# DeepSpace.net
KiCad netlist of a schematic drawn in EAGLE
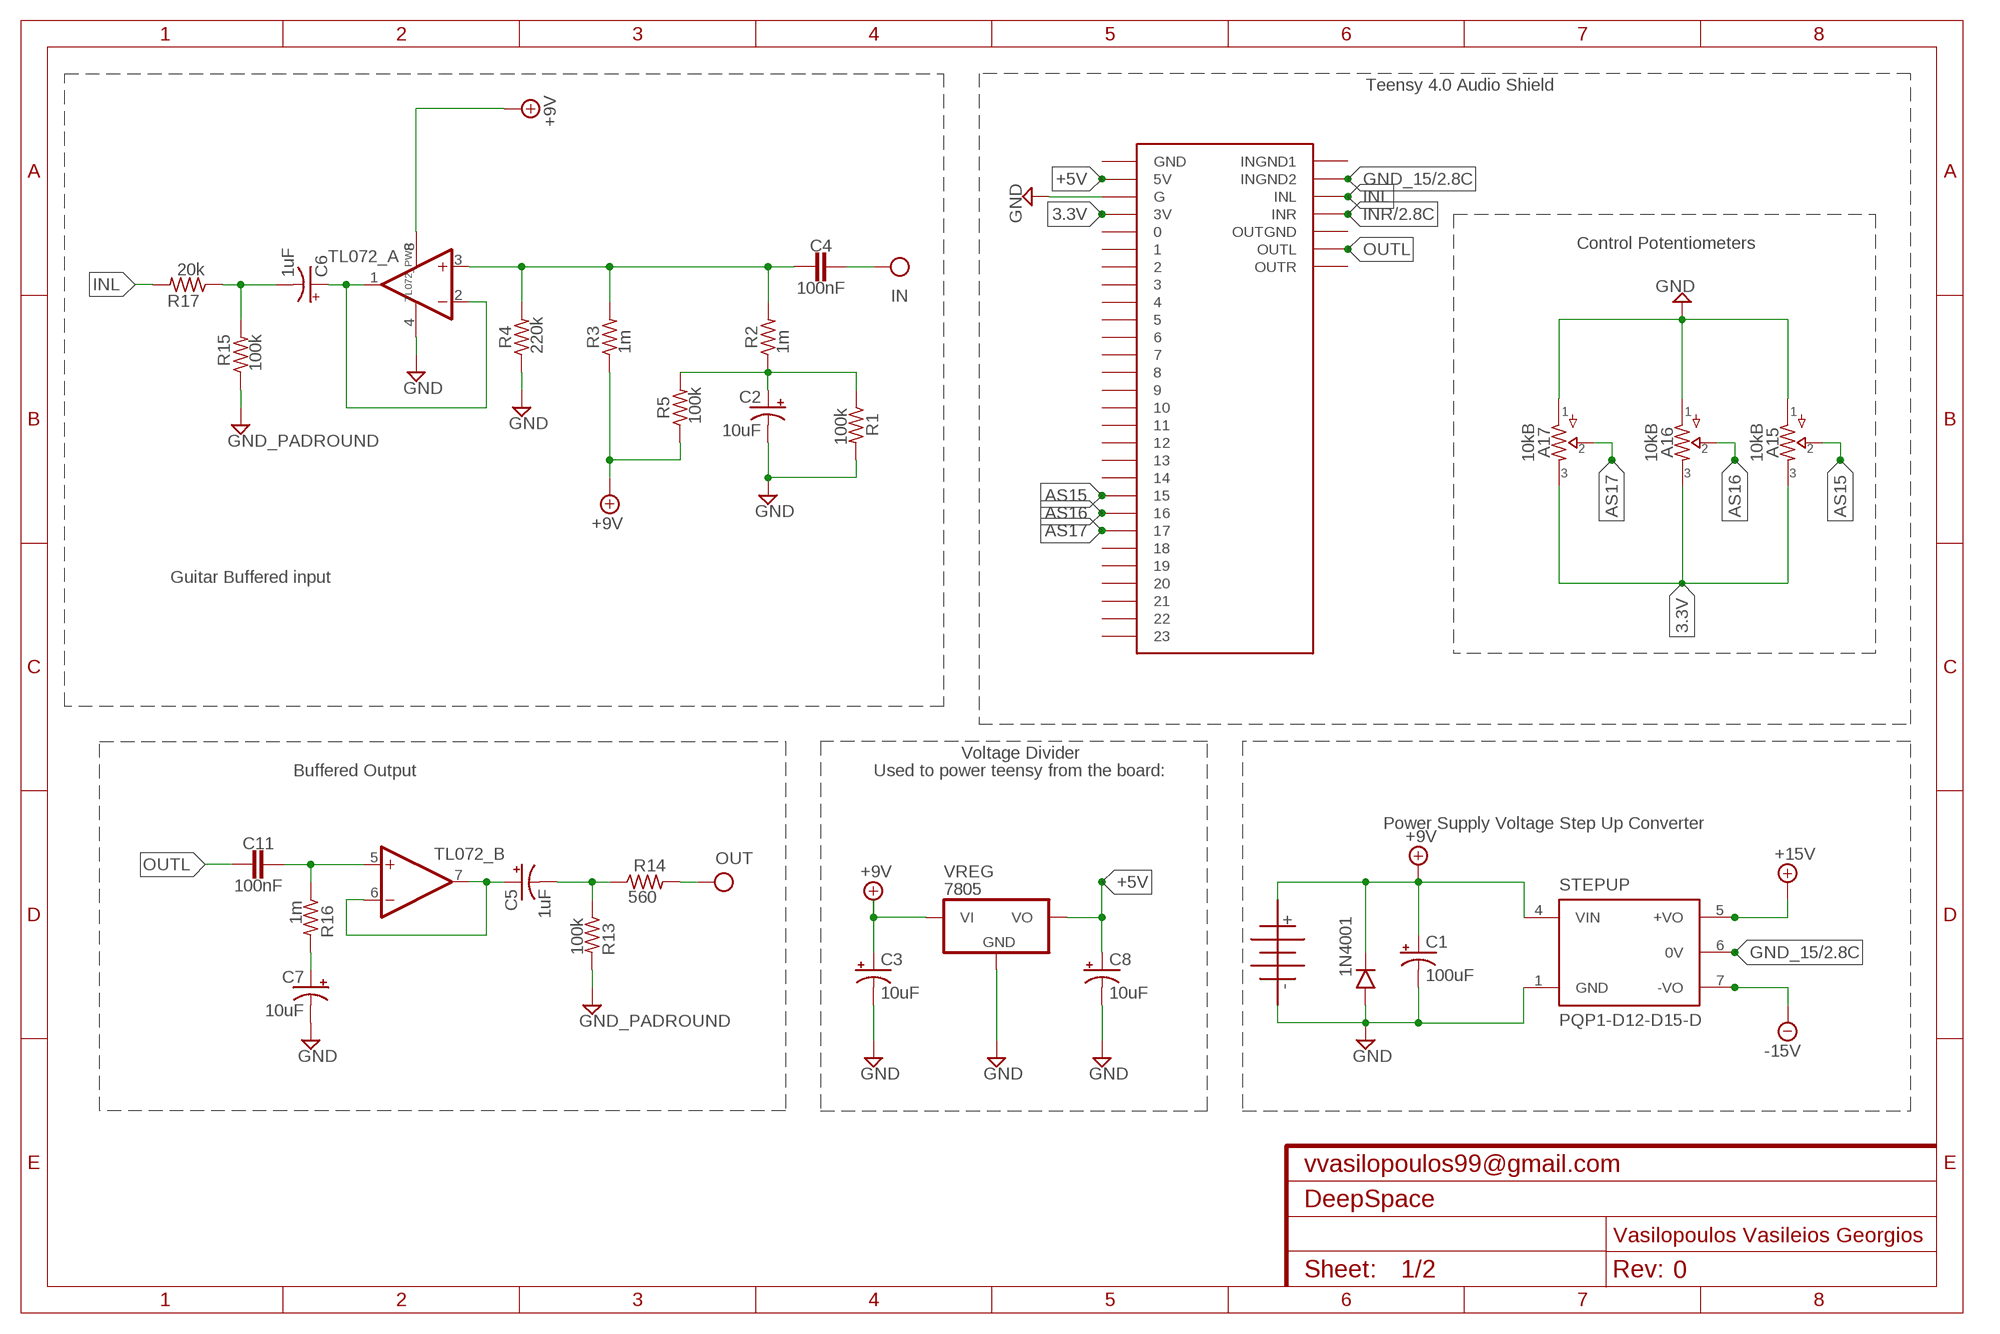
[diagram p0: schematic, sheet 1]
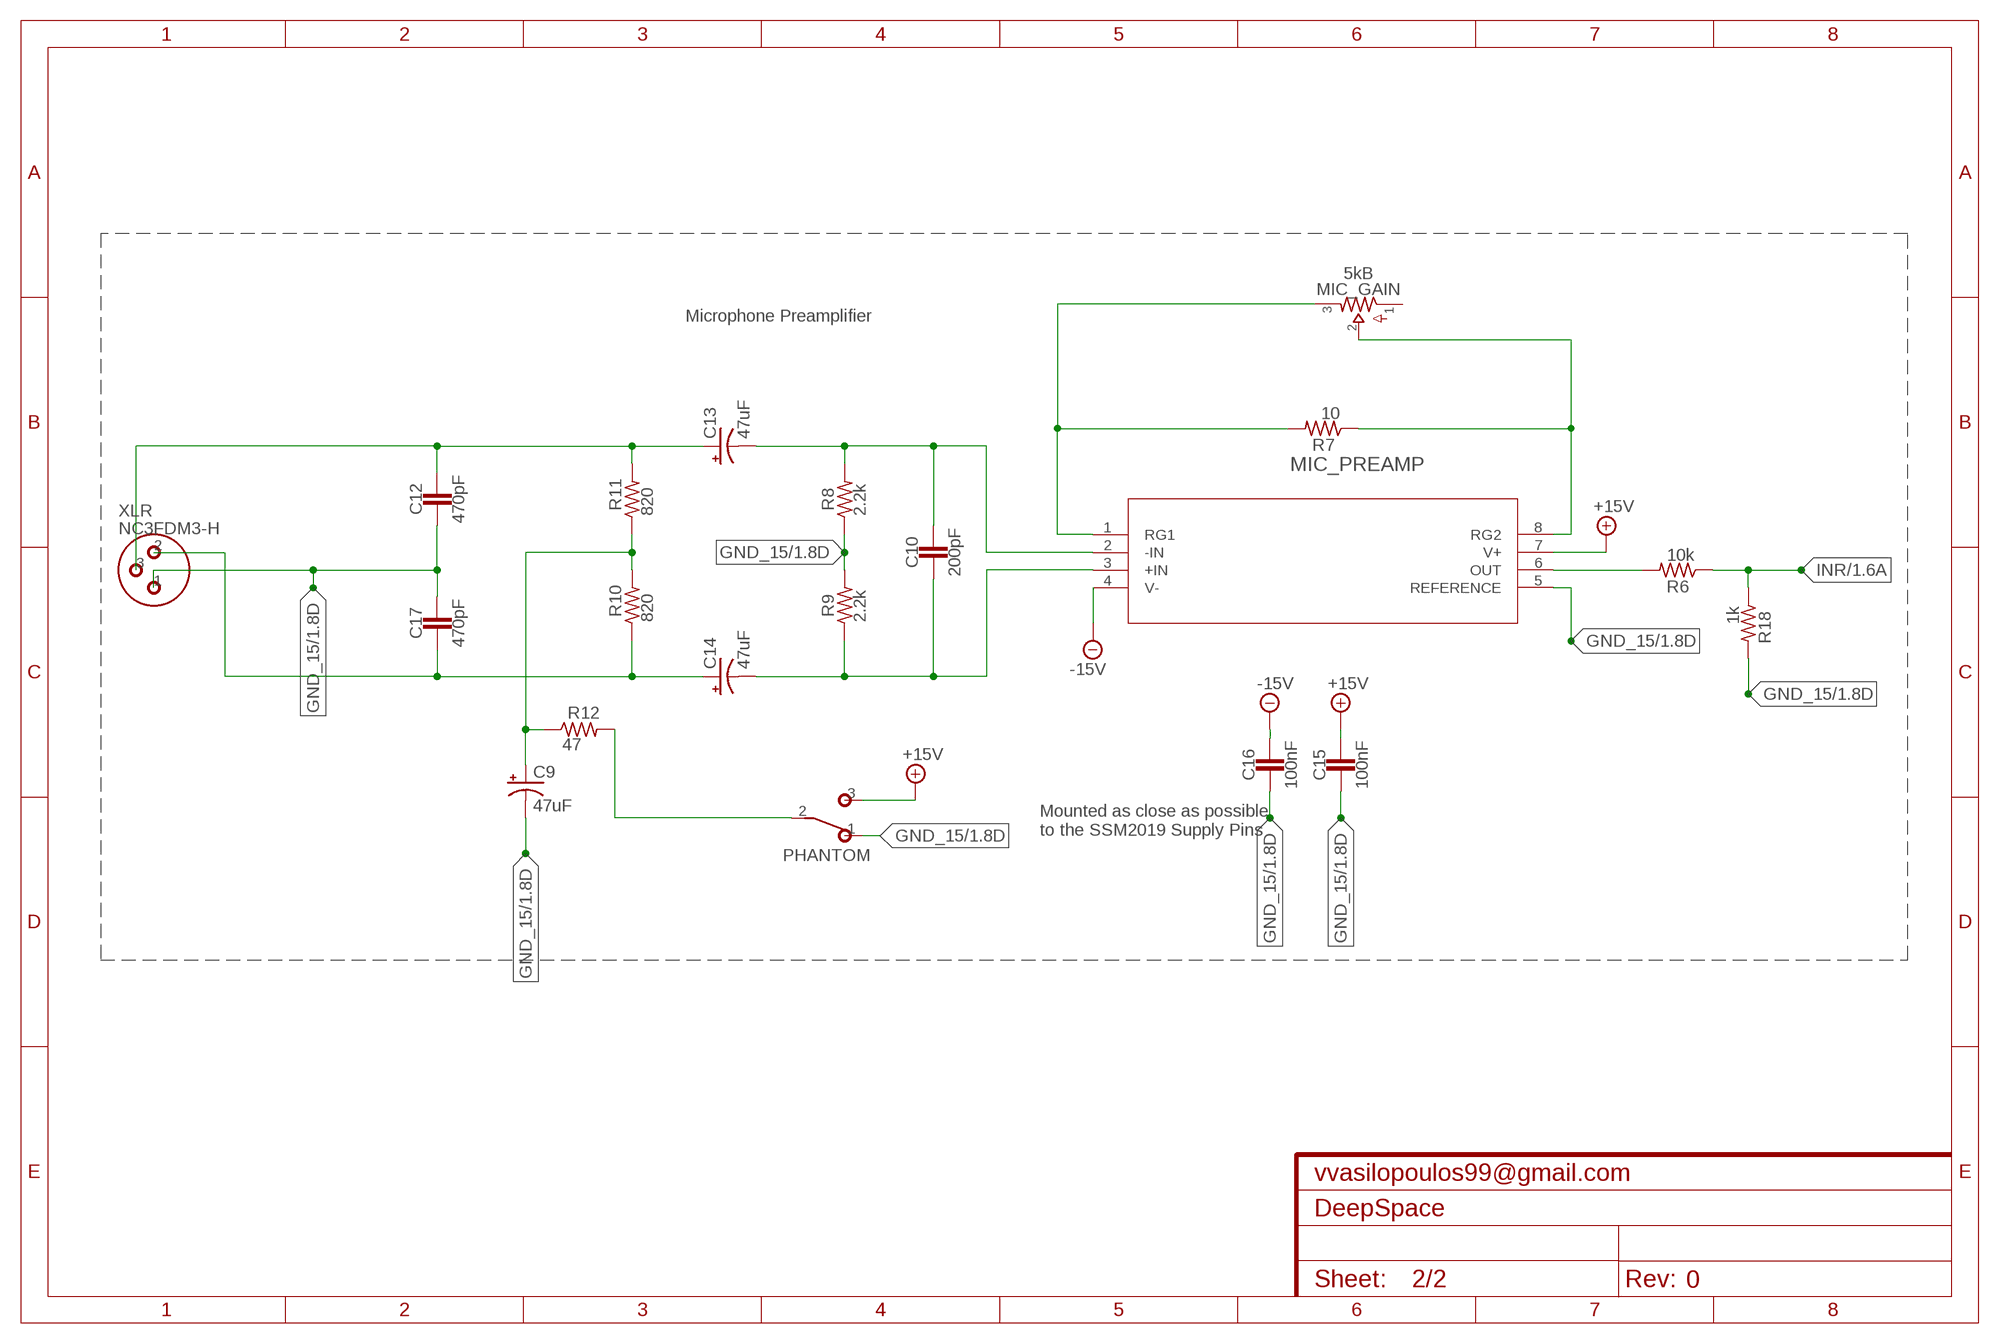
[diagram p1: schematic, sheet 2]

(export (version "E")
  (design (tool "Eeschema 10.0.6"))
  (components
    (comp (ref "C9")
      (value "47uF")
      (footprint "eagle-import:050_020_1")
      (libsource (lib "eagle-import") (part "0501"))
    )
    (comp (ref "C10")
      (value "200pF")
      (footprint "eagle-import:0.2_.SML")
      (libsource (lib "eagle-import") (part "CAP.2"))
    )
    (comp (ref "C12")
      (value "470pF")
      (footprint "eagle-import:0.2_.SML")
      (libsource (lib "eagle-import") (part "CAP.2"))
    )
    (comp (ref "C13")
      (value "47uF")
      (footprint "eagle-import:063_025")
      (libsource (lib "eagle-import") (part "0631"))
    )
    (comp (ref "C14")
      (value "47uF")
      (footprint "eagle-import:063_025")
      (libsource (lib "eagle-import") (part "0631"))
    )
    (comp (ref "C15")
      (value "100nF")
      (footprint "eagle-import:0.2_.SML")
      (libsource (lib "eagle-import") (part "CAP.2"))
    )
    (comp (ref "C16")
      (value "100nF")
      (footprint "eagle-import:0.2_.SML")
      (libsource (lib "eagle-import") (part "CAP.2"))
    )
    (comp (ref "C17")
      (value "470pF")
      (footprint "eagle-import:0.2_.SML")
      (libsource (lib "eagle-import") (part "CAP.2"))
    )
    (comp (ref "MIC_GAIN")
      (value "5kB")
      (footprint "eagle-import:TRIM1")
      (libsource (lib "eagle-import") (part "TRIMMER"))
    )
    (comp (ref "MIC_PREAMP")
      (value "SSM2019BNZ")
      (footprint "eagle-import:N_8_ADI")
      (fields (field (name "MF") "ANALOG DEVICES") (field (name "MPN") "SSM2019BRNZ"))
      (libsource (lib "eagle-import") (part "SSM2019BNZ"))
    )
    (comp (ref "PHANTOM")
      (value "SPDTPADS")
      (footprint "eagle-import:SPDT")
      (libsource (lib "eagle-import") (part "SPDTPADS"))
    )
    (comp (ref "R6")
      (value "10k")
      (footprint "eagle-import:R0207_3")
      (libsource (lib "eagle-import") (part "RESISTORS.3B"))
    )
    (comp (ref "R7")
      (value "10")
      (footprint "eagle-import:R0207_3")
      (libsource (lib "eagle-import") (part "RESISTORS.3B"))
    )
    (comp (ref "R8")
      (value "2.2k")
      (footprint "eagle-import:R0207_3")
      (libsource (lib "eagle-import") (part "RESISTORS.3B"))
    )
    (comp (ref "R9")
      (value "2.2k")
      (footprint "eagle-import:R0207_3")
      (libsource (lib "eagle-import") (part "RESISTORS.3B"))
    )
    (comp (ref "R10")
      (value "820")
      (footprint "eagle-import:R0207_3")
      (libsource (lib "eagle-import") (part "RESISTORS.3B"))
    )
    (comp (ref "R11")
      (value "820")
      (footprint "eagle-import:R0207_3")
      (libsource (lib "eagle-import") (part "RESISTORS.3B"))
    )
    (comp (ref "R12")
      (value "47")
      (footprint "eagle-import:R0207_3")
      (libsource (lib "eagle-import") (part "RESISTORS.3B"))
    )
    (comp (ref "R18")
      (value "1k")
      (footprint "eagle-import:R0207_3")
      (libsource (lib "eagle-import") (part "RESISTORS.3B"))
    )
    (comp (ref "XLR")
      (value "NC3FDM3-H")
      (footprint "eagle-import:XLR_PADS")
      (libsource (lib "eagle-import") (part "XLR"))
    )
    (comp (ref "1N4001")
      (value "DO41.3")
      (footprint "eagle-import:DO41-3")
      (libsource (lib "eagle-import") (part "DO41.3"))
    )
    (comp (ref "A15")
      (value "10kB")
      (footprint "eagle-import:16MM_B.MOUNT")
      (libsource (lib "eagle-import") (part "16MM.1"))
    )
    (comp (ref "A16")
      (value "10kB")
      (footprint "eagle-import:16MM_B.MOUNT")
      (libsource (lib "eagle-import") (part "16MM.1"))
    )
    (comp (ref "A17")
      (value "10kB")
      (footprint "eagle-import:16MM_B.MOUNT")
      (libsource (lib "eagle-import") (part "16MM.1"))
    )
    (comp (ref "AS1")
      (value "teensy audio shield")
      (footprint "eagle-import:AUDIOSHIELD")
      (fields (field (name "MF") "ADAFRUIT") (field (name "MPN") "4384"))
      (libsource (lib "eagle-import") (part "AUDIOSHIELD"))
    )
    (comp (ref "C1")
      (value "100uF")
      (footprint "eagle-import:063_025")
      (libsource (lib "eagle-import") (part "0631"))
    )
    (comp (ref "C2")
      (value "10uF")
      (footprint "eagle-import:050_020_1")
      (libsource (lib "eagle-import") (part "0501"))
    )
    (comp (ref "C3")
      (value "10uF")
      (footprint "eagle-import:050_020_1")
      (libsource (lib "eagle-import") (part "0501"))
    )
    (comp (ref "C4")
      (value "100nF")
      (footprint "eagle-import:0.2_.SML")
      (libsource (lib "eagle-import") (part "CAP.2"))
    )
    (comp (ref "C5")
      (value "1uF")
      (footprint "eagle-import:050_020_1")
      (libsource (lib "eagle-import") (part "0501"))
    )
    (comp (ref "C6")
      (value "1uF")
      (footprint "eagle-import:050_020_1")
      (libsource (lib "eagle-import") (part "0501"))
    )
    (comp (ref "C7")
      (value "10uF")
      (footprint "eagle-import:050_020_1")
      (libsource (lib "eagle-import") (part "0501"))
    )
    (comp (ref "C8")
      (value "10uF")
      (footprint "eagle-import:050_020_1")
      (libsource (lib "eagle-import") (part "0501"))
    )
    (comp (ref "C11")
      (value "100nF")
      (footprint "eagle-import:0.2_.SML")
      (libsource (lib "eagle-import") (part "CAP.2"))
    )
    (comp (ref "GI")
      (value "GND_PADROUND")
      (footprint "eagle-import:ROUND")
      (libsource (lib "eagle-import") (part "GND_PADROUND"))
    )
    (comp (ref "GO")
      (value "GND_PADROUND")
      (footprint "eagle-import:ROUND")
      (libsource (lib "eagle-import") (part "GND_PADROUND"))
    )
    (comp (ref "OUT")
      (value "OUT")
      (footprint "eagle-import:SQUARE")
      (libsource (lib "eagle-import") (part "OUT"))
    )
    (comp (ref "PWR")
      (value "BATTERYBAT2")
      (footprint "eagle-import:BATTERY2")
      (libsource (lib "eagle-import") (part "BATTERYBAT2"))
    )
    (comp (ref "R1")
      (value "100k")
      (footprint "eagle-import:R0207_3")
      (libsource (lib "eagle-import") (part "RESISTORS.3B"))
    )
    (comp (ref "R2")
      (value "1m")
      (footprint "eagle-import:R0207_3")
      (libsource (lib "eagle-import") (part "RESISTORS.3B"))
    )
    (comp (ref "R3")
      (value "1m")
      (footprint "eagle-import:R0207_3")
      (libsource (lib "eagle-import") (part "RESISTORS.3B"))
    )
    (comp (ref "R4")
      (value "220k")
      (footprint "eagle-import:R0207_3")
      (libsource (lib "eagle-import") (part "RESISTORS.3B"))
    )
    (comp (ref "R5")
      (value "100k")
      (footprint "eagle-import:R0207_3")
      (libsource (lib "eagle-import") (part "RESISTORS.3B"))
    )
    (comp (ref "R13")
      (value "100k")
      (footprint "eagle-import:R0207_3")
      (libsource (lib "eagle-import") (part "RESISTORS.3B"))
    )
    (comp (ref "R14")
      (value "560")
      (footprint "eagle-import:R0207_3")
      (libsource (lib "eagle-import") (part "RESISTORS.3B"))
    )
    (comp (ref "R15")
      (value "100k")
      (footprint "eagle-import:R0207_3")
      (libsource (lib "eagle-import") (part "RESISTORS.3B"))
    )
    (comp (ref "R16")
      (value "1m")
      (footprint "eagle-import:R0207_3")
      (libsource (lib "eagle-import") (part "RESISTORS.3B"))
    )
    (comp (ref "R17")
      (value "20k")
      (footprint "eagle-import:R0207_3")
      (libsource (lib "eagle-import") (part "RESISTORS.3B"))
    )
    (comp (ref "STEPUP")
      (value "PQP1-D12-D15-D")
      (footprint "eagle-import:CONV_PQP1-D12-D15-D")
      (fields (field (name "MANUFACTURER") "CUI Inc."))
      (libsource (lib "eagle-import") (part "PQP1-D12-D15-D"))
    )
    (comp (ref "TL072")
      (value "DUALTH")
      (footprint "eagle-import:DIL08")
      (libsource (lib "eagle-import") (part "DUALTH"))
    )
    (comp (ref "VREG")
      (value "7805")
      (footprint "eagle-import:TO92-")
      (libsource (lib "eagle-import") (part "7805"))
    )
    (comp (ref "ΙΝ")
      (value "IN")
      (footprint "eagle-import:SQUARE")
      (libsource (lib "eagle-import") (part "IN"))
    )
  )
  (nets
    (net (code "1") (name "+5V") (class "Default")
      (node (ref "AS1") (pin "5V") (pinfunction "5V_5V") (pintype "bidirectional"))
      (node (ref "C8") (pin "+") (pinfunction "+_+") (pintype "passive"))
      (node (ref "VREG") (pin "3") (pinfunction "VO_3") (pintype "passive"))
    )
    (net (code "2") (name "+9V") (class "Default")
      (node (ref "1N4001") (pin "C") (pinfunction "C_C") (pintype "passive"))
      (node (ref "C1") (pin "+") (pinfunction "+_+") (pintype "passive"))
      (node (ref "C3") (pin "+") (pinfunction "+_+") (pintype "passive"))
      (node (ref "PWR") (pin "P$1") (pinfunction "P$1_P$1") (pintype "bidirectional"))
      (node (ref "R3") (pin "1") (pinfunction "1_1") (pintype "passive"))
      (node (ref "R5") (pin "1") (pinfunction "1_1") (pintype "passive"))
      (node (ref "STEPUP") (pin "4") (pinfunction "VIN_4") (pintype "input"))
      (node (ref "TL072") (pin "8") (pinfunction "V+_8") (pintype "power_in"))
      (node (ref "VREG") (pin "1") (pinfunction "VI_1") (pintype "input"))
    )
    (net (code "3") (name "+15V") (class "Default")
      (node (ref "C15") (pin "1") (pinfunction "1_1") (pintype "passive"))
      (node (ref "MIC_PREAMP") (pin "7") (pinfunction "V+_7") (pintype "power_in"))
      (node (ref "PHANTOM") (pin "3") (pinfunction "S_3") (pintype "passive"))
      (node (ref "STEPUP") (pin "5") (pinfunction "+VO_5") (pintype "output"))
    )
    (net (code "4") (name "-VC") (class "Default")
      (node (ref "C16") (pin "1") (pinfunction "1_1") (pintype "passive"))
      (node (ref "MIC_PREAMP") (pin "4") (pinfunction "V-_4") (pintype "power_in"))
      (node (ref "STEPUP") (pin "7") (pinfunction "-VO_7") (pintype "output"))
    )
    (net (code "5") (name "3.3V") (class "Default")
      (node (ref "A15") (pin "3") (pinfunction "3_3") (pintype "passive"))
      (node (ref "A16") (pin "3") (pinfunction "3_3") (pintype "passive"))
      (node (ref "A17") (pin "3") (pinfunction "3_3") (pintype "passive"))
      (node (ref "AS1") (pin "3V") (pinfunction "3V_3V") (pintype "bidirectional"))
    )
    (net (code "6") (name "AS15") (class "Default")
      (node (ref "A15") (pin "2") (pinfunction "2_2") (pintype "passive"))
      (node (ref "AS1") (pin "15") (pinfunction "15_15") (pintype "bidirectional"))
    )
    (net (code "7") (name "AS16") (class "Default")
      (node (ref "A16") (pin "2") (pinfunction "2_2") (pintype "passive"))
      (node (ref "AS1") (pin "16") (pinfunction "16_16") (pintype "bidirectional"))
    )
    (net (code "8") (name "AS17") (class "Default")
      (node (ref "A17") (pin "2") (pinfunction "2_2") (pintype "passive"))
      (node (ref "AS1") (pin "17") (pinfunction "17_17") (pintype "bidirectional"))
    )
    (net (code "9") (name "GND") (class "Default")
      (node (ref "1N4001") (pin "A") (pinfunction "A_A") (pintype "passive"))
      (node (ref "A15") (pin "1") (pinfunction "1_1") (pintype "passive"))
      (node (ref "A16") (pin "1") (pinfunction "1_1") (pintype "passive"))
      (node (ref "A17") (pin "1") (pinfunction "1_1") (pintype "passive"))
      (node (ref "AS1") (pin "G") (pinfunction "G_G") (pintype "bidirectional"))
      (node (ref "C1") (pin "-") (pinfunction "-_-") (pintype "passive"))
      (node (ref "C2") (pin "-") (pinfunction "-_-") (pintype "passive"))
      (node (ref "C3") (pin "-") (pinfunction "-_-") (pintype "passive"))
      (node (ref "C7") (pin "-") (pinfunction "-_-") (pintype "passive"))
      (node (ref "C8") (pin "-") (pinfunction "-_-") (pintype "passive"))
      (node (ref "GI") (pin "1") (pinfunction "GND_1") (pintype "power_in"))
      (node (ref "GO") (pin "1") (pinfunction "GND_1") (pintype "power_in"))
      (node (ref "PWR") (pin "P$2") (pinfunction "P$2_P$2") (pintype "bidirectional"))
      (node (ref "R1") (pin "2") (pinfunction "2_2") (pintype "passive"))
      (node (ref "R13") (pin "2") (pinfunction "2_2") (pintype "passive"))
      (node (ref "R15") (pin "1") (pinfunction "1_1") (pintype "passive"))
      (node (ref "R4") (pin "1") (pinfunction "1_1") (pintype "passive"))
      (node (ref "STEPUP") (pin "1") (pinfunction "GND_1") (pintype "power_in"))
      (node (ref "TL072") (pin "4") (pinfunction "V-_4") (pintype "power_in"))
      (node (ref "VREG") (pin "2") (pinfunction "GND_2") (pintype "passive"))
    )
    (net (code "10") (name "GND_15") (class "Default")
      (node (ref "AS1") (pin "INGND2") (pinfunction "INGND2_INGND2") (pintype "bidirectional"))
      (node (ref "C12") (pin "2") (pinfunction "2_2") (pintype "passive"))
      (node (ref "C15") (pin "2") (pinfunction "2_2") (pintype "passive"))
      (node (ref "C16") (pin "2") (pinfunction "2_2") (pintype "passive"))
      (node (ref "C17") (pin "1") (pinfunction "1_1") (pintype "passive"))
      (node (ref "C9") (pin "-") (pinfunction "-_-") (pintype "passive"))
      (node (ref "MIC_PREAMP") (pin "5") (pinfunction "REFERENCE_5") (pintype "passive"))
      (node (ref "PHANTOM") (pin "1") (pinfunction "O_1") (pintype "passive"))
      (node (ref "R18") (pin "2") (pinfunction "2_2") (pintype "passive"))
      (node (ref "R8") (pin "1") (pinfunction "1_1") (pintype "passive"))
      (node (ref "R9") (pin "2") (pinfunction "2_2") (pintype "passive"))
      (node (ref "STEPUP") (pin "6") (pinfunction "0V_6") (pintype "output"))
      (node (ref "XLR") (pin "1") (pinfunction "1_1") (pintype "passive"))
    )
    (net (code "11") (name "IN") (class "Default")
      (node (ref "C4") (pin "1") (pinfunction "1_1") (pintype "passive"))
      (node (ref "ΙΝ") (pin "1") (pinfunction "IN_1") (pintype "power_in"))
    )
    (net (code "12") (name "INL") (class "Default")
      (node (ref "AS1") (pin "INL") (pinfunction "INL_INL") (pintype "input"))
      (node (ref "R17") (pin "2") (pinfunction "2_2") (pintype "passive"))
    )
    (net (code "13") (name "INR") (class "Default")
      (node (ref "AS1") (pin "INR") (pinfunction "INR_INR") (pintype "input"))
      (node (ref "R18") (pin "1") (pinfunction "1_1") (pintype "passive"))
      (node (ref "R6") (pin "1") (pinfunction "1_1") (pintype "passive"))
    )
    (net (code "14") (name "Net-(C2-Pad+)") (class "Default")
      (node (ref "C2") (pin "+") (pinfunction "+_+") (pintype "passive"))
      (node (ref "R1") (pin "1") (pinfunction "1_1") (pintype "passive"))
      (node (ref "R2") (pin "1") (pinfunction "1_1") (pintype "passive"))
      (node (ref "R5") (pin "2") (pinfunction "2_2") (pintype "passive"))
    )
    (net (code "15") (name "Net-(C5-Pad-)") (class "Default")
      (node (ref "C5") (pin "-") (pinfunction "-_-") (pintype "passive"))
      (node (ref "R13") (pin "1") (pinfunction "1_1") (pintype "passive"))
      (node (ref "R14") (pin "1") (pinfunction "1_1") (pintype "passive"))
    )
    (net (code "16") (name "Net-(C6-Pad-)") (class "Default")
      (node (ref "C6") (pin "-") (pinfunction "-_-") (pintype "passive"))
      (node (ref "R15") (pin "2") (pinfunction "2_2") (pintype "passive"))
      (node (ref "R17") (pin "1") (pinfunction "1_1") (pintype "passive"))
    )
    (net (code "17") (name "Net-(C7-Pad+)") (class "Default")
      (node (ref "C7") (pin "+") (pinfunction "+_+") (pintype "passive"))
      (node (ref "R16") (pin "2") (pinfunction "2_2") (pintype "passive"))
    )
    (net (code "18") (name "Net-(C9-Pad+)") (class "Default")
      (node (ref "C9") (pin "+") (pinfunction "+_+") (pintype "passive"))
      (node (ref "R10") (pin "2") (pinfunction "2_2") (pintype "passive"))
      (node (ref "R11") (pin "1") (pinfunction "1_1") (pintype "passive"))
      (node (ref "R12") (pin "1") (pinfunction "1_1") (pintype "passive"))
    )
    (net (code "19") (name "Net-(C12-Pad1)") (class "Default")
      (node (ref "C12") (pin "1") (pinfunction "1_1") (pintype "passive"))
      (node (ref "C13") (pin "+") (pinfunction "+_+") (pintype "passive"))
      (node (ref "R11") (pin "2") (pinfunction "2_2") (pintype "passive"))
      (node (ref "XLR") (pin "3") (pinfunction "3_3") (pintype "passive"))
    )
    (net (code "20") (name "Net-(C14-Pad+)") (class "Default")
      (node (ref "C14") (pin "+") (pinfunction "+_+") (pintype "passive"))
      (node (ref "C17") (pin "2") (pinfunction "2_2") (pintype "passive"))
      (node (ref "R10") (pin "1") (pinfunction "1_1") (pintype "passive"))
      (node (ref "XLR") (pin "2") (pinfunction "2_2") (pintype "passive"))
    )
    (net (code "21") (name "Net-(MIC_PREAMP-+IN)") (class "Default")
      (node (ref "C10") (pin "2") (pinfunction "2_2") (pintype "passive"))
      (node (ref "C14") (pin "-") (pinfunction "-_-") (pintype "passive"))
      (node (ref "MIC_PREAMP") (pin "3") (pinfunction "+IN_3") (pintype "passive"))
      (node (ref "R9") (pin "1") (pinfunction "1_1") (pintype "passive"))
    )
    (net (code "22") (name "Net-(MIC_PREAMP--IN)") (class "Default")
      (node (ref "C10") (pin "1") (pinfunction "1_1") (pintype "passive"))
      (node (ref "C13") (pin "-") (pinfunction "-_-") (pintype "passive"))
      (node (ref "MIC_PREAMP") (pin "2") (pinfunction "-IN_2") (pintype "passive"))
      (node (ref "R8") (pin "2") (pinfunction "2_2") (pintype "passive"))
    )
    (net (code "23") (name "Net-(MIC_PREAMP-OUT)") (class "Default")
      (node (ref "MIC_PREAMP") (pin "6") (pinfunction "OUT_6") (pintype "passive"))
      (node (ref "R6") (pin "2") (pinfunction "2_2") (pintype "passive"))
    )
    (net (code "24") (name "Net-(MIC_PREAMP-RG1)") (class "Default")
      (node (ref "MIC_GAIN") (pin "3") (pinfunction "3_3") (pintype "passive"))
      (node (ref "MIC_PREAMP") (pin "1") (pinfunction "RG1_1") (pintype "passive"))
      (node (ref "R7") (pin "2") (pinfunction "2_2") (pintype "passive"))
    )
    (net (code "25") (name "Net-(MIC_PREAMP-RG2)") (class "Default")
      (node (ref "MIC_GAIN") (pin "2") (pinfunction "2_2") (pintype "passive"))
      (node (ref "MIC_PREAMP") (pin "8") (pinfunction "RG2_8") (pintype "passive"))
      (node (ref "R7") (pin "1") (pinfunction "1_1") (pintype "passive"))
    )
    (net (code "26") (name "Net-(PHANTOM-P)") (class "Default")
      (node (ref "PHANTOM") (pin "2") (pinfunction "P_2") (pintype "passive"))
      (node (ref "R12") (pin "2") (pinfunction "2_2") (pintype "passive"))
    )
    (net (code "27") (name "Net-(TL072A-+IN)") (class "Default")
      (node (ref "C4") (pin "2") (pinfunction "2_2") (pintype "passive"))
      (node (ref "R2") (pin "2") (pinfunction "2_2") (pintype "passive"))
      (node (ref "R3") (pin "2") (pinfunction "2_2") (pintype "passive"))
      (node (ref "R4") (pin "2") (pinfunction "2_2") (pintype "passive"))
      (node (ref "TL072") (pin "3") (pinfunction "+IN_3") (pintype "input"))
    )
    (net (code "28") (name "Net-(TL072A--IN)") (class "Default")
      (node (ref "C6") (pin "+") (pinfunction "+_+") (pintype "passive"))
      (node (ref "TL072") (pin "1") (pinfunction "OUT_1") (pintype "output"))
      (node (ref "TL072") (pin "2") (pinfunction "-IN_2") (pintype "input"))
    )
    (net (code "29") (name "Net-(TL072B-+IN)") (class "Default")
      (node (ref "C11") (pin "1") (pinfunction "1_1") (pintype "passive"))
      (node (ref "R16") (pin "1") (pinfunction "1_1") (pintype "passive"))
      (node (ref "TL072") (pin "5") (pinfunction "+IN_5") (pintype "input"))
    )
    (net (code "30") (name "Net-(TL072B--IN)") (class "Default")
      (node (ref "C5") (pin "+") (pinfunction "+_+") (pintype "passive"))
      (node (ref "TL072") (pin "6") (pinfunction "-IN_6") (pintype "input"))
      (node (ref "TL072") (pin "7") (pinfunction "OUT_7") (pintype "output"))
    )
    (net (code "31") (name "OUT") (class "Default")
      (node (ref "OUT") (pin "1") (pinfunction "OUT_1") (pintype "power_in"))
      (node (ref "R14") (pin "2") (pinfunction "2_2") (pintype "passive"))
    )
    (net (code "32") (name "OUTL") (class "Default")
      (node (ref "AS1") (pin "OUTL") (pinfunction "OUTL_OUTL") (pintype "output"))
      (node (ref "C11") (pin "2") (pinfunction "2_2") (pintype "passive"))
    )
    (net (code "33") (name "unconnected-(AS1-Pad0)") (class "Default")
      (node (ref "AS1") (pin "0") (pinfunction "0_0") (pintype "bidirectional"))
    )
    (net (code "34") (name "unconnected-(AS1-Pad1)") (class "Default")
      (node (ref "AS1") (pin "1") (pinfunction "1_1") (pintype "bidirectional"))
    )
    (net (code "35") (name "unconnected-(AS1-Pad2)") (class "Default")
      (node (ref "AS1") (pin "2") (pinfunction "2_2") (pintype "bidirectional"))
    )
    (net (code "36") (name "unconnected-(AS1-Pad3)") (class "Default")
      (node (ref "AS1") (pin "3") (pinfunction "3_3") (pintype "bidirectional"))
    )
    (net (code "37") (name "unconnected-(AS1-Pad4)") (class "Default")
      (node (ref "AS1") (pin "4") (pinfunction "4_4") (pintype "bidirectional"))
    )
    (net (code "38") (name "unconnected-(AS1-Pad5)") (class "Default")
      (node (ref "AS1") (pin "5") (pinfunction "5_5") (pintype "bidirectional"))
    )
    (net (code "39") (name "unconnected-(AS1-Pad6)") (class "Default")
      (node (ref "AS1") (pin "6") (pinfunction "6_6") (pintype "bidirectional"))
    )
    (net (code "40") (name "unconnected-(AS1-Pad7)") (class "Default")
      (node (ref "AS1") (pin "7") (pinfunction "7_7") (pintype "bidirectional"))
    )
    (net (code "41") (name "unconnected-(AS1-Pad8)") (class "Default")
      (node (ref "AS1") (pin "8") (pinfunction "8_8") (pintype "bidirectional"))
    )
    (net (code "42") (name "unconnected-(AS1-Pad9)") (class "Default")
      (node (ref "AS1") (pin "9") (pinfunction "9_9") (pintype "bidirectional"))
    )
    (net (code "43") (name "unconnected-(AS1-Pad10)") (class "Default")
      (node (ref "AS1") (pin "10") (pinfunction "10_10") (pintype "bidirectional"))
    )
    (net (code "44") (name "unconnected-(AS1-Pad11)") (class "Default")
      (node (ref "AS1") (pin "11") (pinfunction "11_11") (pintype "bidirectional"))
    )
    (net (code "45") (name "unconnected-(AS1-Pad12)") (class "Default")
      (node (ref "AS1") (pin "12") (pinfunction "12_12") (pintype "bidirectional"))
    )
    (net (code "46") (name "unconnected-(AS1-Pad13)") (class "Default")
      (node (ref "AS1") (pin "13") (pinfunction "13_13") (pintype "bidirectional"))
    )
    (net (code "47") (name "unconnected-(AS1-Pad14)") (class "Default")
      (node (ref "AS1") (pin "14") (pinfunction "14_14") (pintype "bidirectional"))
    )
    (net (code "48") (name "unconnected-(AS1-Pad18)") (class "Default")
      (node (ref "AS1") (pin "18") (pinfunction "18_18") (pintype "bidirectional"))
    )
    (net (code "49") (name "unconnected-(AS1-Pad19)") (class "Default")
      (node (ref "AS1") (pin "19") (pinfunction "19_19") (pintype "bidirectional"))
    )
    (net (code "50") (name "unconnected-(AS1-Pad20)") (class "Default")
      (node (ref "AS1") (pin "20") (pinfunction "20_20") (pintype "bidirectional"))
    )
    (net (code "51") (name "unconnected-(AS1-Pad21)") (class "Default")
      (node (ref "AS1") (pin "21") (pinfunction "21_21") (pintype "bidirectional"))
    )
    (net (code "52") (name "unconnected-(AS1-Pad22)") (class "Default")
      (node (ref "AS1") (pin "22") (pinfunction "22_22") (pintype "bidirectional"))
    )
    (net (code "53") (name "unconnected-(AS1-Pad23)") (class "Default")
      (node (ref "AS1") (pin "23") (pinfunction "23_23") (pintype "bidirectional"))
    )
    (net (code "54") (name "unconnected-(AS1-PadGND)") (class "Default")
      (node (ref "AS1") (pin "GND") (pinfunction "GND_GND") (pintype "bidirectional"))
    )
    (net (code "55") (name "unconnected-(AS1-PadINGND1)") (class "Default")
      (node (ref "AS1") (pin "INGND1") (pinfunction "INGND1_INGND1") (pintype "bidirectional"))
    )
    (net (code "56") (name "unconnected-(AS1-PadOUTGND)") (class "Default")
      (node (ref "AS1") (pin "OUTGND") (pinfunction "OUTGND_OUTGND") (pintype "bidirectional"))
    )
    (net (code "57") (name "unconnected-(AS1-PadOUTR)") (class "Default")
      (node (ref "AS1") (pin "OUTR") (pinfunction "OUTR_OUTR") (pintype "output"))
    )
    (net (code "58") (name "unconnected-(MIC_GAIN-Pad1)") (class "Default")
      (node (ref "MIC_GAIN") (pin "1") (pinfunction "1_1") (pintype "passive"))
    )
  )
)
